# FLD_Logic.net
KiCad netlist of a schematic drawn in EAGLE
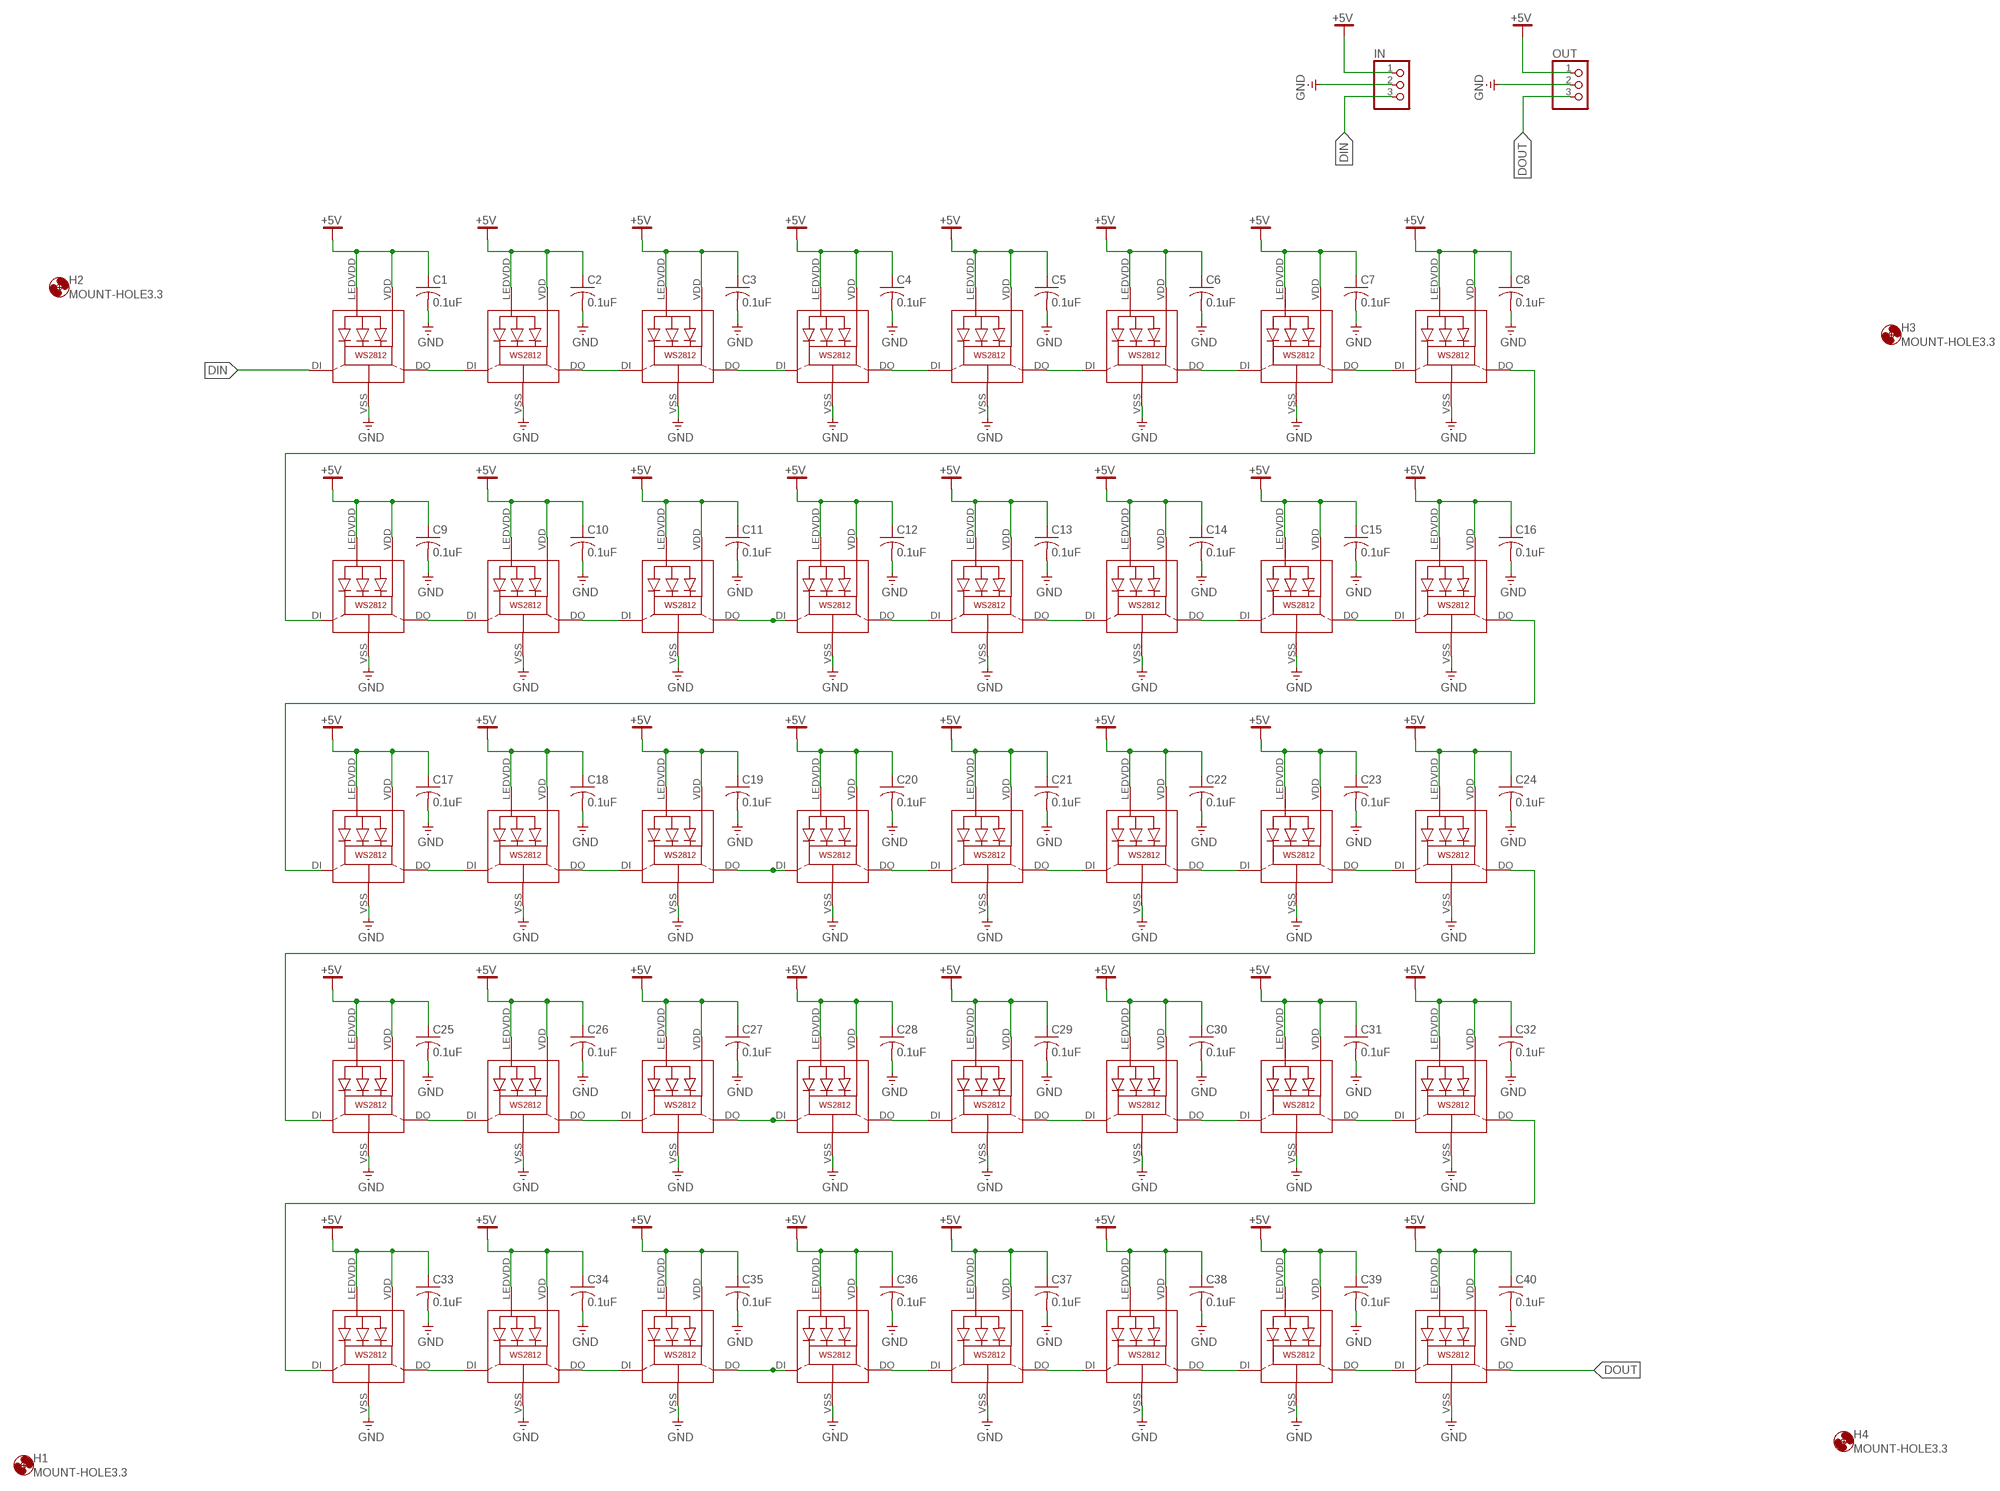
[diagram p0: schematic, sheet 1]

(export (version "E")
  (design (tool "Eeschema 10.0.6"))
  (components
    (comp (ref "C1")
      (value "0.1uF")
      (footprint "eagle-import:C0603")
      (libsource (lib "eagle-import") (part "C-USC0603"))
    )
    (comp (ref "C2")
      (value "0.1uF")
      (footprint "eagle-import:C0603")
      (libsource (lib "eagle-import") (part "C-USC0603"))
    )
    (comp (ref "C3")
      (value "0.1uF")
      (footprint "eagle-import:C0603")
      (libsource (lib "eagle-import") (part "C-USC0603"))
    )
    (comp (ref "C4")
      (value "0.1uF")
      (footprint "eagle-import:C0603")
      (libsource (lib "eagle-import") (part "C-USC0603"))
    )
    (comp (ref "C5")
      (value "0.1uF")
      (footprint "eagle-import:C0603")
      (libsource (lib "eagle-import") (part "C-USC0603"))
    )
    (comp (ref "C6")
      (value "0.1uF")
      (footprint "eagle-import:C0603")
      (libsource (lib "eagle-import") (part "C-USC0603"))
    )
    (comp (ref "C7")
      (value "0.1uF")
      (footprint "eagle-import:C0603")
      (libsource (lib "eagle-import") (part "C-USC0603"))
    )
    (comp (ref "C8")
      (value "0.1uF")
      (footprint "eagle-import:C0603")
      (libsource (lib "eagle-import") (part "C-USC0603"))
    )
    (comp (ref "C9")
      (value "0.1uF")
      (footprint "eagle-import:C0603")
      (libsource (lib "eagle-import") (part "C-USC0603"))
    )
    (comp (ref "C10")
      (value "0.1uF")
      (footprint "eagle-import:C0603")
      (libsource (lib "eagle-import") (part "C-USC0603"))
    )
    (comp (ref "C11")
      (value "0.1uF")
      (footprint "eagle-import:C0603")
      (libsource (lib "eagle-import") (part "C-USC0603"))
    )
    (comp (ref "C12")
      (value "0.1uF")
      (footprint "eagle-import:C0603")
      (libsource (lib "eagle-import") (part "C-USC0603"))
    )
    (comp (ref "C13")
      (value "0.1uF")
      (footprint "eagle-import:C0603")
      (libsource (lib "eagle-import") (part "C-USC0603"))
    )
    (comp (ref "C14")
      (value "0.1uF")
      (footprint "eagle-import:C0603")
      (libsource (lib "eagle-import") (part "C-USC0603"))
    )
    (comp (ref "C15")
      (value "0.1uF")
      (footprint "eagle-import:C0603")
      (libsource (lib "eagle-import") (part "C-USC0603"))
    )
    (comp (ref "C16")
      (value "0.1uF")
      (footprint "eagle-import:C0603")
      (libsource (lib "eagle-import") (part "C-USC0603"))
    )
    (comp (ref "C17")
      (value "0.1uF")
      (footprint "eagle-import:C0603")
      (libsource (lib "eagle-import") (part "C-USC0603"))
    )
    (comp (ref "C18")
      (value "0.1uF")
      (footprint "eagle-import:C0603")
      (libsource (lib "eagle-import") (part "C-USC0603"))
    )
    (comp (ref "C19")
      (value "0.1uF")
      (footprint "eagle-import:C0603")
      (libsource (lib "eagle-import") (part "C-USC0603"))
    )
    (comp (ref "C20")
      (value "0.1uF")
      (footprint "eagle-import:C0603")
      (libsource (lib "eagle-import") (part "C-USC0603"))
    )
    (comp (ref "C21")
      (value "0.1uF")
      (footprint "eagle-import:C0603")
      (libsource (lib "eagle-import") (part "C-USC0603"))
    )
    (comp (ref "C22")
      (value "0.1uF")
      (footprint "eagle-import:C0603")
      (libsource (lib "eagle-import") (part "C-USC0603"))
    )
    (comp (ref "C23")
      (value "0.1uF")
      (footprint "eagle-import:C0603")
      (libsource (lib "eagle-import") (part "C-USC0603"))
    )
    (comp (ref "C24")
      (value "0.1uF")
      (footprint "eagle-import:C0603")
      (libsource (lib "eagle-import") (part "C-USC0603"))
    )
    (comp (ref "C25")
      (value "0.1uF")
      (footprint "eagle-import:C0603")
      (libsource (lib "eagle-import") (part "C-USC0603"))
    )
    (comp (ref "C26")
      (value "0.1uF")
      (footprint "eagle-import:C0603")
      (libsource (lib "eagle-import") (part "C-USC0603"))
    )
    (comp (ref "C27")
      (value "0.1uF")
      (footprint "eagle-import:C0603")
      (libsource (lib "eagle-import") (part "C-USC0603"))
    )
    (comp (ref "C28")
      (value "0.1uF")
      (footprint "eagle-import:C0603")
      (libsource (lib "eagle-import") (part "C-USC0603"))
    )
    (comp (ref "C29")
      (value "0.1uF")
      (footprint "eagle-import:C0603")
      (libsource (lib "eagle-import") (part "C-USC0603"))
    )
    (comp (ref "C30")
      (value "0.1uF")
      (footprint "eagle-import:C0603")
      (libsource (lib "eagle-import") (part "C-USC0603"))
    )
    (comp (ref "C31")
      (value "0.1uF")
      (footprint "eagle-import:C0603")
      (libsource (lib "eagle-import") (part "C-USC0603"))
    )
    (comp (ref "C32")
      (value "0.1uF")
      (footprint "eagle-import:C0603")
      (libsource (lib "eagle-import") (part "C-USC0603"))
    )
    (comp (ref "C33")
      (value "0.1uF")
      (footprint "eagle-import:C0603")
      (libsource (lib "eagle-import") (part "C-USC0603"))
    )
    (comp (ref "C34")
      (value "0.1uF")
      (footprint "eagle-import:C0603")
      (libsource (lib "eagle-import") (part "C-USC0603"))
    )
    (comp (ref "C35")
      (value "0.1uF")
      (footprint "eagle-import:C0603")
      (libsource (lib "eagle-import") (part "C-USC0603"))
    )
    (comp (ref "C36")
      (value "0.1uF")
      (footprint "eagle-import:C0603")
      (libsource (lib "eagle-import") (part "C-USC0603"))
    )
    (comp (ref "C37")
      (value "0.1uF")
      (footprint "eagle-import:C0603")
      (libsource (lib "eagle-import") (part "C-USC0603"))
    )
    (comp (ref "C38")
      (value "0.1uF")
      (footprint "eagle-import:C0603")
      (libsource (lib "eagle-import") (part "C-USC0603"))
    )
    (comp (ref "C39")
      (value "0.1uF")
      (footprint "eagle-import:C0603")
      (libsource (lib "eagle-import") (part "C-USC0603"))
    )
    (comp (ref "C40")
      (value "0.1uF")
      (footprint "eagle-import:C0603")
      (libsource (lib "eagle-import") (part "C-USC0603"))
    )
    (comp (ref "H1")
      (value "MOUNT-HOLE3.3")
      (footprint "eagle-import:3,3")
      (libsource (lib "eagle-import") (part "MOUNT-HOLE3.3"))
    )
    (comp (ref "H2")
      (value "MOUNT-HOLE3.3")
      (footprint "eagle-import:3,3")
      (libsource (lib "eagle-import") (part "MOUNT-HOLE3.3"))
    )
    (comp (ref "H3")
      (value "MOUNT-HOLE3.3")
      (footprint "eagle-import:3,3")
      (libsource (lib "eagle-import") (part "MOUNT-HOLE3.3"))
    )
    (comp (ref "H4")
      (value "MOUNT-HOLE3.3")
      (footprint "eagle-import:3,3")
      (libsource (lib "eagle-import") (part "MOUNT-HOLE3.3"))
    )
    (comp (ref "IN")
      (value "PINHD-1X3")
      (footprint "eagle-import:1X03")
      (libsource (lib "eagle-import") (part "PINHD-1X3"))
    )
    (comp (ref "LED1")
      (value "WS2812")
      (footprint "eagle-import:WS2812")
      (libsource (lib "eagle-import") (part "WS2812"))
    )
    (comp (ref "LED2")
      (value "WS2812")
      (footprint "eagle-import:WS2812")
      (libsource (lib "eagle-import") (part "WS2812"))
    )
    (comp (ref "LED3")
      (value "WS2812")
      (footprint "eagle-import:WS2812")
      (libsource (lib "eagle-import") (part "WS2812"))
    )
    (comp (ref "LED4")
      (value "WS2812")
      (footprint "eagle-import:WS2812")
      (libsource (lib "eagle-import") (part "WS2812"))
    )
    (comp (ref "LED5")
      (value "WS2812")
      (footprint "eagle-import:WS2812")
      (libsource (lib "eagle-import") (part "WS2812"))
    )
    (comp (ref "LED6")
      (value "WS2812")
      (footprint "eagle-import:WS2812")
      (libsource (lib "eagle-import") (part "WS2812"))
    )
    (comp (ref "LED7")
      (value "WS2812")
      (footprint "eagle-import:WS2812")
      (libsource (lib "eagle-import") (part "WS2812"))
    )
    (comp (ref "LED8")
      (value "WS2812")
      (footprint "eagle-import:WS2812")
      (libsource (lib "eagle-import") (part "WS2812"))
    )
    (comp (ref "LED9")
      (value "WS2812")
      (footprint "eagle-import:WS2812")
      (libsource (lib "eagle-import") (part "WS2812"))
    )
    (comp (ref "LED10")
      (value "WS2812")
      (footprint "eagle-import:WS2812")
      (libsource (lib "eagle-import") (part "WS2812"))
    )
    (comp (ref "LED11")
      (value "WS2812")
      (footprint "eagle-import:WS2812")
      (libsource (lib "eagle-import") (part "WS2812"))
    )
    (comp (ref "LED12")
      (value "WS2812")
      (footprint "eagle-import:WS2812")
      (libsource (lib "eagle-import") (part "WS2812"))
    )
    (comp (ref "LED13")
      (value "WS2812")
      (footprint "eagle-import:WS2812")
      (libsource (lib "eagle-import") (part "WS2812"))
    )
    (comp (ref "LED14")
      (value "WS2812")
      (footprint "eagle-import:WS2812")
      (libsource (lib "eagle-import") (part "WS2812"))
    )
    (comp (ref "LED15")
      (value "WS2812")
      (footprint "eagle-import:WS2812")
      (libsource (lib "eagle-import") (part "WS2812"))
    )
    (comp (ref "LED16")
      (value "WS2812")
      (footprint "eagle-import:WS2812")
      (libsource (lib "eagle-import") (part "WS2812"))
    )
    (comp (ref "LED17")
      (value "WS2812")
      (footprint "eagle-import:WS2812")
      (libsource (lib "eagle-import") (part "WS2812"))
    )
    (comp (ref "LED18")
      (value "WS2812")
      (footprint "eagle-import:WS2812")
      (libsource (lib "eagle-import") (part "WS2812"))
    )
    (comp (ref "LED19")
      (value "WS2812")
      (footprint "eagle-import:WS2812")
      (libsource (lib "eagle-import") (part "WS2812"))
    )
    (comp (ref "LED20")
      (value "WS2812")
      (footprint "eagle-import:WS2812")
      (libsource (lib "eagle-import") (part "WS2812"))
    )
    (comp (ref "LED21")
      (value "WS2812")
      (footprint "eagle-import:WS2812")
      (libsource (lib "eagle-import") (part "WS2812"))
    )
    (comp (ref "LED22")
      (value "WS2812")
      (footprint "eagle-import:WS2812")
      (libsource (lib "eagle-import") (part "WS2812"))
    )
    (comp (ref "LED23")
      (value "WS2812")
      (footprint "eagle-import:WS2812")
      (libsource (lib "eagle-import") (part "WS2812"))
    )
    (comp (ref "LED24")
      (value "WS2812")
      (footprint "eagle-import:WS2812")
      (libsource (lib "eagle-import") (part "WS2812"))
    )
    (comp (ref "LED25")
      (value "WS2812")
      (footprint "eagle-import:WS2812")
      (libsource (lib "eagle-import") (part "WS2812"))
    )
    (comp (ref "LED26")
      (value "WS2812")
      (footprint "eagle-import:WS2812")
      (libsource (lib "eagle-import") (part "WS2812"))
    )
    (comp (ref "LED27")
      (value "WS2812")
      (footprint "eagle-import:WS2812")
      (libsource (lib "eagle-import") (part "WS2812"))
    )
    (comp (ref "LED28")
      (value "WS2812")
      (footprint "eagle-import:WS2812")
      (libsource (lib "eagle-import") (part "WS2812"))
    )
    (comp (ref "LED29")
      (value "WS2812")
      (footprint "eagle-import:WS2812")
      (libsource (lib "eagle-import") (part "WS2812"))
    )
    (comp (ref "LED30")
      (value "WS2812")
      (footprint "eagle-import:WS2812")
      (libsource (lib "eagle-import") (part "WS2812"))
    )
    (comp (ref "LED31")
      (value "WS2812")
      (footprint "eagle-import:WS2812")
      (libsource (lib "eagle-import") (part "WS2812"))
    )
    (comp (ref "LED32")
      (value "WS2812")
      (footprint "eagle-import:WS2812")
      (libsource (lib "eagle-import") (part "WS2812"))
    )
    (comp (ref "LED33")
      (value "WS2812")
      (footprint "eagle-import:WS2812")
      (libsource (lib "eagle-import") (part "WS2812"))
    )
    (comp (ref "LED34")
      (value "WS2812")
      (footprint "eagle-import:WS2812")
      (libsource (lib "eagle-import") (part "WS2812"))
    )
    (comp (ref "LED35")
      (value "WS2812")
      (footprint "eagle-import:WS2812")
      (libsource (lib "eagle-import") (part "WS2812"))
    )
    (comp (ref "LED36")
      (value "WS2812")
      (footprint "eagle-import:WS2812")
      (libsource (lib "eagle-import") (part "WS2812"))
    )
    (comp (ref "LED37")
      (value "WS2812")
      (footprint "eagle-import:WS2812")
      (libsource (lib "eagle-import") (part "WS2812"))
    )
    (comp (ref "LED38")
      (value "WS2812")
      (footprint "eagle-import:WS2812")
      (libsource (lib "eagle-import") (part "WS2812"))
    )
    (comp (ref "LED39")
      (value "WS2812")
      (footprint "eagle-import:WS2812")
      (libsource (lib "eagle-import") (part "WS2812"))
    )
    (comp (ref "LED40")
      (value "WS2812")
      (footprint "eagle-import:WS2812")
      (libsource (lib "eagle-import") (part "WS2812"))
    )
    (comp (ref "OUT")
      (value "PINHD-1X3")
      (footprint "eagle-import:1X03")
      (libsource (lib "eagle-import") (part "PINHD-1X3"))
    )
  )
  (nets
    (net (code "1") (name "+5V") (class "Default")
      (node (ref "C1") (pin "1") (pinfunction "1_1") (pintype "passive"))
      (node (ref "C10") (pin "1") (pinfunction "1_1") (pintype "passive"))
      (node (ref "C11") (pin "1") (pinfunction "1_1") (pintype "passive"))
      (node (ref "C12") (pin "1") (pinfunction "1_1") (pintype "passive"))
      (node (ref "C13") (pin "1") (pinfunction "1_1") (pintype "passive"))
      (node (ref "C14") (pin "1") (pinfunction "1_1") (pintype "passive"))
      (node (ref "C15") (pin "1") (pinfunction "1_1") (pintype "passive"))
      (node (ref "C16") (pin "1") (pinfunction "1_1") (pintype "passive"))
      (node (ref "C17") (pin "1") (pinfunction "1_1") (pintype "passive"))
      (node (ref "C18") (pin "1") (pinfunction "1_1") (pintype "passive"))
      (node (ref "C19") (pin "1") (pinfunction "1_1") (pintype "passive"))
      (node (ref "C2") (pin "1") (pinfunction "1_1") (pintype "passive"))
      (node (ref "C20") (pin "1") (pinfunction "1_1") (pintype "passive"))
      (node (ref "C21") (pin "1") (pinfunction "1_1") (pintype "passive"))
      (node (ref "C22") (pin "1") (pinfunction "1_1") (pintype "passive"))
      (node (ref "C23") (pin "1") (pinfunction "1_1") (pintype "passive"))
      (node (ref "C24") (pin "1") (pinfunction "1_1") (pintype "passive"))
      (node (ref "C25") (pin "1") (pinfunction "1_1") (pintype "passive"))
      (node (ref "C26") (pin "1") (pinfunction "1_1") (pintype "passive"))
      (node (ref "C27") (pin "1") (pinfunction "1_1") (pintype "passive"))
      (node (ref "C28") (pin "1") (pinfunction "1_1") (pintype "passive"))
      (node (ref "C29") (pin "1") (pinfunction "1_1") (pintype "passive"))
      (node (ref "C3") (pin "1") (pinfunction "1_1") (pintype "passive"))
      (node (ref "C30") (pin "1") (pinfunction "1_1") (pintype "passive"))
      (node (ref "C31") (pin "1") (pinfunction "1_1") (pintype "passive"))
      (node (ref "C32") (pin "1") (pinfunction "1_1") (pintype "passive"))
      (node (ref "C33") (pin "1") (pinfunction "1_1") (pintype "passive"))
      (node (ref "C34") (pin "1") (pinfunction "1_1") (pintype "passive"))
      (node (ref "C35") (pin "1") (pinfunction "1_1") (pintype "passive"))
      (node (ref "C36") (pin "1") (pinfunction "1_1") (pintype "passive"))
      (node (ref "C37") (pin "1") (pinfunction "1_1") (pintype "passive"))
      (node (ref "C38") (pin "1") (pinfunction "1_1") (pintype "passive"))
      (node (ref "C39") (pin "1") (pinfunction "1_1") (pintype "passive"))
      (node (ref "C4") (pin "1") (pinfunction "1_1") (pintype "passive"))
      (node (ref "C40") (pin "1") (pinfunction "1_1") (pintype "passive"))
      (node (ref "C5") (pin "1") (pinfunction "1_1") (pintype "passive"))
      (node (ref "C6") (pin "1") (pinfunction "1_1") (pintype "passive"))
      (node (ref "C7") (pin "1") (pinfunction "1_1") (pintype "passive"))
      (node (ref "C8") (pin "1") (pinfunction "1_1") (pintype "passive"))
      (node (ref "C9") (pin "1") (pinfunction "1_1") (pintype "passive"))
      (node (ref "IN") (pin "1") (pinfunction "1_1") (pintype "passive"))
      (node (ref "LED1") (pin "LEDVDD") (pinfunction "LEDVDD_LEDVDD") (pintype "power_in"))
      (node (ref "LED1") (pin "VDD") (pinfunction "VDD_VDD") (pintype "power_in"))
      (node (ref "LED10") (pin "LEDVDD") (pinfunction "LEDVDD_LEDVDD") (pintype "power_in"))
      (node (ref "LED10") (pin "VDD") (pinfunction "VDD_VDD") (pintype "power_in"))
      (node (ref "LED11") (pin "LEDVDD") (pinfunction "LEDVDD_LEDVDD") (pintype "power_in"))
      (node (ref "LED11") (pin "VDD") (pinfunction "VDD_VDD") (pintype "power_in"))
      (node (ref "LED12") (pin "LEDVDD") (pinfunction "LEDVDD_LEDVDD") (pintype "power_in"))
      (node (ref "LED12") (pin "VDD") (pinfunction "VDD_VDD") (pintype "power_in"))
      (node (ref "LED13") (pin "LEDVDD") (pinfunction "LEDVDD_LEDVDD") (pintype "power_in"))
      (node (ref "LED13") (pin "VDD") (pinfunction "VDD_VDD") (pintype "power_in"))
      (node (ref "LED14") (pin "LEDVDD") (pinfunction "LEDVDD_LEDVDD") (pintype "power_in"))
      (node (ref "LED14") (pin "VDD") (pinfunction "VDD_VDD") (pintype "power_in"))
      (node (ref "LED15") (pin "LEDVDD") (pinfunction "LEDVDD_LEDVDD") (pintype "power_in"))
      (node (ref "LED15") (pin "VDD") (pinfunction "VDD_VDD") (pintype "power_in"))
      (node (ref "LED16") (pin "LEDVDD") (pinfunction "LEDVDD_LEDVDD") (pintype "power_in"))
      (node (ref "LED16") (pin "VDD") (pinfunction "VDD_VDD") (pintype "power_in"))
      (node (ref "LED17") (pin "LEDVDD") (pinfunction "LEDVDD_LEDVDD") (pintype "power_in"))
      (node (ref "LED17") (pin "VDD") (pinfunction "VDD_VDD") (pintype "power_in"))
      (node (ref "LED18") (pin "LEDVDD") (pinfunction "LEDVDD_LEDVDD") (pintype "power_in"))
      (node (ref "LED18") (pin "VDD") (pinfunction "VDD_VDD") (pintype "power_in"))
      (node (ref "LED19") (pin "LEDVDD") (pinfunction "LEDVDD_LEDVDD") (pintype "power_in"))
      (node (ref "LED19") (pin "VDD") (pinfunction "VDD_VDD") (pintype "power_in"))
      (node (ref "LED2") (pin "LEDVDD") (pinfunction "LEDVDD_LEDVDD") (pintype "power_in"))
      (node (ref "LED2") (pin "VDD") (pinfunction "VDD_VDD") (pintype "power_in"))
      (node (ref "LED20") (pin "LEDVDD") (pinfunction "LEDVDD_LEDVDD") (pintype "power_in"))
      (node (ref "LED20") (pin "VDD") (pinfunction "VDD_VDD") (pintype "power_in"))
      (node (ref "LED21") (pin "LEDVDD") (pinfunction "LEDVDD_LEDVDD") (pintype "power_in"))
      (node (ref "LED21") (pin "VDD") (pinfunction "VDD_VDD") (pintype "power_in"))
      (node (ref "LED22") (pin "LEDVDD") (pinfunction "LEDVDD_LEDVDD") (pintype "power_in"))
      (node (ref "LED22") (pin "VDD") (pinfunction "VDD_VDD") (pintype "power_in"))
      (node (ref "LED23") (pin "LEDVDD") (pinfunction "LEDVDD_LEDVDD") (pintype "power_in"))
      (node (ref "LED23") (pin "VDD") (pinfunction "VDD_VDD") (pintype "power_in"))
      (node (ref "LED24") (pin "LEDVDD") (pinfunction "LEDVDD_LEDVDD") (pintype "power_in"))
      (node (ref "LED24") (pin "VDD") (pinfunction "VDD_VDD") (pintype "power_in"))
      (node (ref "LED25") (pin "LEDVDD") (pinfunction "LEDVDD_LEDVDD") (pintype "power_in"))
      (node (ref "LED25") (pin "VDD") (pinfunction "VDD_VDD") (pintype "power_in"))
      (node (ref "LED26") (pin "LEDVDD") (pinfunction "LEDVDD_LEDVDD") (pintype "power_in"))
      (node (ref "LED26") (pin "VDD") (pinfunction "VDD_VDD") (pintype "power_in"))
      (node (ref "LED27") (pin "LEDVDD") (pinfunction "LEDVDD_LEDVDD") (pintype "power_in"))
      (node (ref "LED27") (pin "VDD") (pinfunction "VDD_VDD") (pintype "power_in"))
      (node (ref "LED28") (pin "LEDVDD") (pinfunction "LEDVDD_LEDVDD") (pintype "power_in"))
      (node (ref "LED28") (pin "VDD") (pinfunction "VDD_VDD") (pintype "power_in"))
      (node (ref "LED29") (pin "LEDVDD") (pinfunction "LEDVDD_LEDVDD") (pintype "power_in"))
      (node (ref "LED29") (pin "VDD") (pinfunction "VDD_VDD") (pintype "power_in"))
      (node (ref "LED3") (pin "LEDVDD") (pinfunction "LEDVDD_LEDVDD") (pintype "power_in"))
      (node (ref "LED3") (pin "VDD") (pinfunction "VDD_VDD") (pintype "power_in"))
      (node (ref "LED30") (pin "LEDVDD") (pinfunction "LEDVDD_LEDVDD") (pintype "power_in"))
      (node (ref "LED30") (pin "VDD") (pinfunction "VDD_VDD") (pintype "power_in"))
      (node (ref "LED31") (pin "LEDVDD") (pinfunction "LEDVDD_LEDVDD") (pintype "power_in"))
      (node (ref "LED31") (pin "VDD") (pinfunction "VDD_VDD") (pintype "power_in"))
      (node (ref "LED32") (pin "LEDVDD") (pinfunction "LEDVDD_LEDVDD") (pintype "power_in"))
      (node (ref "LED32") (pin "VDD") (pinfunction "VDD_VDD") (pintype "power_in"))
      (node (ref "LED33") (pin "LEDVDD") (pinfunction "LEDVDD_LEDVDD") (pintype "power_in"))
      (node (ref "LED33") (pin "VDD") (pinfunction "VDD_VDD") (pintype "power_in"))
      (node (ref "LED34") (pin "LEDVDD") (pinfunction "LEDVDD_LEDVDD") (pintype "power_in"))
      (node (ref "LED34") (pin "VDD") (pinfunction "VDD_VDD") (pintype "power_in"))
      (node (ref "LED35") (pin "LEDVDD") (pinfunction "LEDVDD_LEDVDD") (pintype "power_in"))
      (node (ref "LED35") (pin "VDD") (pinfunction "VDD_VDD") (pintype "power_in"))
      (node (ref "LED36") (pin "LEDVDD") (pinfunction "LEDVDD_LEDVDD") (pintype "power_in"))
      (node (ref "LED36") (pin "VDD") (pinfunction "VDD_VDD") (pintype "power_in"))
      (node (ref "LED37") (pin "LEDVDD") (pinfunction "LEDVDD_LEDVDD") (pintype "power_in"))
      (node (ref "LED37") (pin "VDD") (pinfunction "VDD_VDD") (pintype "power_in"))
      (node (ref "LED38") (pin "LEDVDD") (pinfunction "LEDVDD_LEDVDD") (pintype "power_in"))
      (node (ref "LED38") (pin "VDD") (pinfunction "VDD_VDD") (pintype "power_in"))
      (node (ref "LED39") (pin "LEDVDD") (pinfunction "LEDVDD_LEDVDD") (pintype "power_in"))
      (node (ref "LED39") (pin "VDD") (pinfunction "VDD_VDD") (pintype "power_in"))
      (node (ref "LED4") (pin "LEDVDD") (pinfunction "LEDVDD_LEDVDD") (pintype "power_in"))
      (node (ref "LED4") (pin "VDD") (pinfunction "VDD_VDD") (pintype "power_in"))
      (node (ref "LED40") (pin "LEDVDD") (pinfunction "LEDVDD_LEDVDD") (pintype "power_in"))
      (node (ref "LED40") (pin "VDD") (pinfunction "VDD_VDD") (pintype "power_in"))
      (node (ref "LED5") (pin "LEDVDD") (pinfunction "LEDVDD_LEDVDD") (pintype "power_in"))
      (node (ref "LED5") (pin "VDD") (pinfunction "VDD_VDD") (pintype "power_in"))
      (node (ref "LED6") (pin "LEDVDD") (pinfunction "LEDVDD_LEDVDD") (pintype "power_in"))
      (node (ref "LED6") (pin "VDD") (pinfunction "VDD_VDD") (pintype "power_in"))
      (node (ref "LED7") (pin "LEDVDD") (pinfunction "LEDVDD_LEDVDD") (pintype "power_in"))
      (node (ref "LED7") (pin "VDD") (pinfunction "VDD_VDD") (pintype "power_in"))
      (node (ref "LED8") (pin "LEDVDD") (pinfunction "LEDVDD_LEDVDD") (pintype "power_in"))
      (node (ref "LED8") (pin "VDD") (pinfunction "VDD_VDD") (pintype "power_in"))
      (node (ref "LED9") (pin "LEDVDD") (pinfunction "LEDVDD_LEDVDD") (pintype "power_in"))
      (node (ref "LED9") (pin "VDD") (pinfunction "VDD_VDD") (pintype "power_in"))
      (node (ref "OUT") (pin "1") (pinfunction "1_1") (pintype "passive"))
    )
    (net (code "2") (name "DIN") (class "Default")
      (node (ref "IN") (pin "3") (pinfunction "3_3") (pintype "passive"))
      (node (ref "LED1") (pin "DI") (pinfunction "DI_DI") (pintype "input"))
    )
    (net (code "3") (name "DOUT") (class "Default")
      (node (ref "LED40") (pin "DO") (pinfunction "DO_DO") (pintype "output"))
      (node (ref "OUT") (pin "3") (pinfunction "3_3") (pintype "passive"))
    )
    (net (code "4") (name "GND") (class "Default")
      (node (ref "C1") (pin "2") (pinfunction "2_2") (pintype "passive"))
      (node (ref "C10") (pin "2") (pinfunction "2_2") (pintype "passive"))
      (node (ref "C11") (pin "2") (pinfunction "2_2") (pintype "passive"))
      (node (ref "C12") (pin "2") (pinfunction "2_2") (pintype "passive"))
      (node (ref "C13") (pin "2") (pinfunction "2_2") (pintype "passive"))
      (node (ref "C14") (pin "2") (pinfunction "2_2") (pintype "passive"))
      (node (ref "C15") (pin "2") (pinfunction "2_2") (pintype "passive"))
      (node (ref "C16") (pin "2") (pinfunction "2_2") (pintype "passive"))
      (node (ref "C17") (pin "2") (pinfunction "2_2") (pintype "passive"))
      (node (ref "C18") (pin "2") (pinfunction "2_2") (pintype "passive"))
      (node (ref "C19") (pin "2") (pinfunction "2_2") (pintype "passive"))
      (node (ref "C2") (pin "2") (pinfunction "2_2") (pintype "passive"))
      (node (ref "C20") (pin "2") (pinfunction "2_2") (pintype "passive"))
      (node (ref "C21") (pin "2") (pinfunction "2_2") (pintype "passive"))
      (node (ref "C22") (pin "2") (pinfunction "2_2") (pintype "passive"))
      (node (ref "C23") (pin "2") (pinfunction "2_2") (pintype "passive"))
      (node (ref "C24") (pin "2") (pinfunction "2_2") (pintype "passive"))
      (node (ref "C25") (pin "2") (pinfunction "2_2") (pintype "passive"))
      (node (ref "C26") (pin "2") (pinfunction "2_2") (pintype "passive"))
      (node (ref "C27") (pin "2") (pinfunction "2_2") (pintype "passive"))
      (node (ref "C28") (pin "2") (pinfunction "2_2") (pintype "passive"))
      (node (ref "C29") (pin "2") (pinfunction "2_2") (pintype "passive"))
      (node (ref "C3") (pin "2") (pinfunction "2_2") (pintype "passive"))
      (node (ref "C30") (pin "2") (pinfunction "2_2") (pintype "passive"))
      (node (ref "C31") (pin "2") (pinfunction "2_2") (pintype "passive"))
      (node (ref "C32") (pin "2") (pinfunction "2_2") (pintype "passive"))
      (node (ref "C33") (pin "2") (pinfunction "2_2") (pintype "passive"))
      (node (ref "C34") (pin "2") (pinfunction "2_2") (pintype "passive"))
      (node (ref "C35") (pin "2") (pinfunction "2_2") (pintype "passive"))
      (node (ref "C36") (pin "2") (pinfunction "2_2") (pintype "passive"))
      (node (ref "C37") (pin "2") (pinfunction "2_2") (pintype "passive"))
      (node (ref "C38") (pin "2") (pinfunction "2_2") (pintype "passive"))
      (node (ref "C39") (pin "2") (pinfunction "2_2") (pintype "passive"))
      (node (ref "C4") (pin "2") (pinfunction "2_2") (pintype "passive"))
      (node (ref "C40") (pin "2") (pinfunction "2_2") (pintype "passive"))
      (node (ref "C5") (pin "2") (pinfunction "2_2") (pintype "passive"))
      (node (ref "C6") (pin "2") (pinfunction "2_2") (pintype "passive"))
      (node (ref "C7") (pin "2") (pinfunction "2_2") (pintype "passive"))
      (node (ref "C8") (pin "2") (pinfunction "2_2") (pintype "passive"))
      (node (ref "C9") (pin "2") (pinfunction "2_2") (pintype "passive"))
      (node (ref "IN") (pin "2") (pinfunction "2_2") (pintype "passive"))
      (node (ref "LED1") (pin "VSS") (pinfunction "GND_VSS") (pintype "power_in"))
      (node (ref "LED10") (pin "VSS") (pinfunction "GND_VSS") (pintype "power_in"))
      (node (ref "LED11") (pin "VSS") (pinfunction "GND_VSS") (pintype "power_in"))
      (node (ref "LED12") (pin "VSS") (pinfunction "GND_VSS") (pintype "power_in"))
      (node (ref "LED13") (pin "VSS") (pinfunction "GND_VSS") (pintype "power_in"))
      (node (ref "LED14") (pin "VSS") (pinfunction "GND_VSS") (pintype "power_in"))
      (node (ref "LED15") (pin "VSS") (pinfunction "GND_VSS") (pintype "power_in"))
      (node (ref "LED16") (pin "VSS") (pinfunction "GND_VSS") (pintype "power_in"))
      (node (ref "LED17") (pin "VSS") (pinfunction "GND_VSS") (pintype "power_in"))
      (node (ref "LED18") (pin "VSS") (pinfunction "GND_VSS") (pintype "power_in"))
      (node (ref "LED19") (pin "VSS") (pinfunction "GND_VSS") (pintype "power_in"))
      (node (ref "LED2") (pin "VSS") (pinfunction "GND_VSS") (pintype "power_in"))
      (node (ref "LED20") (pin "VSS") (pinfunction "GND_VSS") (pintype "power_in"))
      (node (ref "LED21") (pin "VSS") (pinfunction "GND_VSS") (pintype "power_in"))
      (node (ref "LED22") (pin "VSS") (pinfunction "GND_VSS") (pintype "power_in"))
      (node (ref "LED23") (pin "VSS") (pinfunction "GND_VSS") (pintype "power_in"))
      (node (ref "LED24") (pin "VSS") (pinfunction "GND_VSS") (pintype "power_in"))
      (node (ref "LED25") (pin "VSS") (pinfunction "GND_VSS") (pintype "power_in"))
      (node (ref "LED26") (pin "VSS") (pinfunction "GND_VSS") (pintype "power_in"))
      (node (ref "LED27") (pin "VSS") (pinfunction "GND_VSS") (pintype "power_in"))
      (node (ref "LED28") (pin "VSS") (pinfunction "GND_VSS") (pintype "power_in"))
      (node (ref "LED29") (pin "VSS") (pinfunction "GND_VSS") (pintype "power_in"))
      (node (ref "LED3") (pin "VSS") (pinfunction "GND_VSS") (pintype "power_in"))
      (node (ref "LED30") (pin "VSS") (pinfunction "GND_VSS") (pintype "power_in"))
      (node (ref "LED31") (pin "VSS") (pinfunction "GND_VSS") (pintype "power_in"))
      (node (ref "LED32") (pin "VSS") (pinfunction "GND_VSS") (pintype "power_in"))
      (node (ref "LED33") (pin "VSS") (pinfunction "GND_VSS") (pintype "power_in"))
      (node (ref "LED34") (pin "VSS") (pinfunction "GND_VSS") (pintype "power_in"))
      (node (ref "LED35") (pin "VSS") (pinfunction "GND_VSS") (pintype "power_in"))
      (node (ref "LED36") (pin "VSS") (pinfunction "GND_VSS") (pintype "power_in"))
      (node (ref "LED37") (pin "VSS") (pinfunction "GND_VSS") (pintype "power_in"))
      (node (ref "LED38") (pin "VSS") (pinfunction "GND_VSS") (pintype "power_in"))
      (node (ref "LED39") (pin "VSS") (pinfunction "GND_VSS") (pintype "power_in"))
      (node (ref "LED4") (pin "VSS") (pinfunction "GND_VSS") (pintype "power_in"))
      (node (ref "LED40") (pin "VSS") (pinfunction "GND_VSS") (pintype "power_in"))
      (node (ref "LED5") (pin "VSS") (pinfunction "GND_VSS") (pintype "power_in"))
      (node (ref "LED6") (pin "VSS") (pinfunction "GND_VSS") (pintype "power_in"))
      (node (ref "LED7") (pin "VSS") (pinfunction "GND_VSS") (pintype "power_in"))
      (node (ref "LED8") (pin "VSS") (pinfunction "GND_VSS") (pintype "power_in"))
      (node (ref "LED9") (pin "VSS") (pinfunction "GND_VSS") (pintype "power_in"))
      (node (ref "OUT") (pin "2") (pinfunction "2_2") (pintype "passive"))
    )
    (net (code "5") (name "Net-(LED1-PadDO)") (class "Default")
      (node (ref "LED1") (pin "DO") (pinfunction "DO_DO") (pintype "output"))
      (node (ref "LED2") (pin "DI") (pinfunction "DI_DI") (pintype "input"))
    )
    (net (code "6") (name "Net-(LED2-PadDO)") (class "Default")
      (node (ref "LED2") (pin "DO") (pinfunction "DO_DO") (pintype "output"))
      (node (ref "LED3") (pin "DI") (pinfunction "DI_DI") (pintype "input"))
    )
    (net (code "7") (name "Net-(LED4-PadDO)") (class "Default")
      (node (ref "LED4") (pin "DO") (pinfunction "DO_DO") (pintype "output"))
      (node (ref "LED5") (pin "DI") (pinfunction "DI_DI") (pintype "input"))
    )
    (net (code "8") (name "Net-(LED5-PadDO)") (class "Default")
      (node (ref "LED5") (pin "DO") (pinfunction "DO_DO") (pintype "output"))
      (node (ref "LED6") (pin "DI") (pinfunction "DI_DI") (pintype "input"))
    )
    (net (code "9") (name "Net-(LED6-PadDO)") (class "Default")
      (node (ref "LED6") (pin "DO") (pinfunction "DO_DO") (pintype "output"))
      (node (ref "LED7") (pin "DI") (pinfunction "DI_DI") (pintype "input"))
    )
    (net (code "10") (name "Net-(LED7-PadDO)") (class "Default")
      (node (ref "LED7") (pin "DO") (pinfunction "DO_DO") (pintype "output"))
      (node (ref "LED8") (pin "DI") (pinfunction "DI_DI") (pintype "input"))
    )
    (net (code "11") (name "Net-(LED10-PadDI)") (class "Default")
      (node (ref "LED10") (pin "DI") (pinfunction "DI_DI") (pintype "input"))
      (node (ref "LED9") (pin "DO") (pinfunction "DO_DO") (pintype "output"))
    )
    (net (code "12") (name "Net-(LED10-PadDO)") (class "Default")
      (node (ref "LED10") (pin "DO") (pinfunction "DO_DO") (pintype "output"))
      (node (ref "LED11") (pin "DI") (pinfunction "DI_DI") (pintype "input"))
    )
    (net (code "13") (name "Net-(LED11-PadDO)") (class "Default")
      (node (ref "LED11") (pin "DO") (pinfunction "DO_DO") (pintype "output"))
      (node (ref "LED12") (pin "DI") (pinfunction "DI_DI") (pintype "input"))
    )
    (net (code "14") (name "Net-(LED12-PadDO)") (class "Default")
      (node (ref "LED12") (pin "DO") (pinfunction "DO_DO") (pintype "output"))
      (node (ref "LED13") (pin "DI") (pinfunction "DI_DI") (pintype "input"))
    )
    (net (code "15") (name "Net-(LED13-PadDO)") (class "Default")
      (node (ref "LED13") (pin "DO") (pinfunction "DO_DO") (pintype "output"))
      (node (ref "LED14") (pin "DI") (pinfunction "DI_DI") (pintype "input"))
    )
    (net (code "16") (name "Net-(LED14-PadDO)") (class "Default")
      (node (ref "LED14") (pin "DO") (pinfunction "DO_DO") (pintype "output"))
      (node (ref "LED15") (pin "DI") (pinfunction "DI_DI") (pintype "input"))
    )
    (net (code "17") (name "Net-(LED15-PadDO)") (class "Default")
      (node (ref "LED15") (pin "DO") (pinfunction "DO_DO") (pintype "output"))
      (node (ref "LED16") (pin "DI") (pinfunction "DI_DI") (pintype "input"))
    )
    (net (code "18") (name "Net-(LED17-PadDO)") (class "Default")
      (node (ref "LED17") (pin "DO") (pinfunction "DO_DO") (pintype "output"))
      (node (ref "LED18") (pin "DI") (pinfunction "DI_DI") (pintype "input"))
    )
    (net (code "19") (name "Net-(LED18-PadDO)") (class "Default")
      (node (ref "LED18") (pin "DO") (pinfunction "DO_DO") (pintype "output"))
      (node (ref "LED19") (pin "DI") (pinfunction "DI_DI") (pintype "input"))
    )
    (net (code "20") (name "Net-(LED19-PadDO)") (class "Default")
      (node (ref "LED19") (pin "DO") (pinfunction "DO_DO") (pintype "output"))
      (node (ref "LED20") (pin "DI") (pinfunction "DI_DI") (pintype "input"))
    )
    (net (code "21") (name "Net-(LED20-PadDO)") (class "Default")
      (node (ref "LED20") (pin "DO") (pinfunction "DO_DO") (pintype "output"))
      (node (ref "LED21") (pin "DI") (pinfunction "DI_DI") (pintype "input"))
    )
    (net (code "22") (name "Net-(LED21-PadDO)") (class "Default")
      (node (ref "LED21") (pin "DO") (pinfunction "DO_DO") (pintype "output"))
      (node (ref "LED22") (pin "DI") (pinfunction "DI_DI") (pintype "input"))
    )
    (net (code "23") (name "Net-(LED22-PadDO)") (class "Default")
      (node (ref "LED22") (pin "DO") (pinfunction "DO_DO") (pintype "output"))
      (node (ref "LED23") (pin "DI") (pinfunction "DI_DI") (pintype "input"))
    )
    (net (code "24") (name "Net-(LED23-PadDO)") (class "Default")
      (node (ref "LED23") (pin "DO") (pinfunction "DO_DO") (pintype "output"))
      (node (ref "LED24") (pin "DI") (pinfunction "DI_DI") (pintype "input"))
    )
    (net (code "25") (name "Net-(LED25-PadDO)") (class "Default")
      (node (ref "LED25") (pin "DO") (pinfunction "DO_DO") (pintype "output"))
      (node (ref "LED26") (pin "DI") (pinfunction "DI_DI") (pintype "input"))
    )
    (net (code "26") (name "Net-(LED26-PadDO)") (class "Default")
      (node (ref "LED26") (pin "DO") (pinfunction "DO_DO") (pintype "output"))
      (node (ref "LED27") (pin "DI") (pinfunction "DI_DI") (pintype "input"))
    )
    (net (code "27") (name "Net-(LED27-PadDO)") (class "Default")
      (node (ref "LED27") (pin "DO") (pinfunction "DO_DO") (pintype "output"))
      (node (ref "LED28") (pin "DI") (pinfunction "DI_DI") (pintype "input"))
    )
    (net (code "28") (name "Net-(LED28-PadDO)") (class "Default")
      (node (ref "LED28") (pin "DO") (pinfunction "DO_DO") (pintype "output"))
      (node (ref "LED29") (pin "DI") (pinfunction "DI_DI") (pintype "input"))
    )
    (net (code "29") (name "Net-(LED29-PadDO)") (class "Default")
      (node (ref "LED29") (pin "DO") (pinfunction "DO_DO") (pintype "output"))
      (node (ref "LED30") (pin "DI") (pinfunction "DI_DI") (pintype "input"))
    )
    (net (code "30") (name "Net-(LED30-PadDO)") (class "Default")
      (node (ref "LED30") (pin "DO") (pinfunction "DO_DO") (pintype "output"))
      (node (ref "LED31") (pin "DI") (pinfunction "DI_DI") (pintype "input"))
    )
    (net (code "31") (name "Net-(LED31-PadDO)") (class "Default")
      (node (ref "LED31") (pin "DO") (pinfunction "DO_DO") (pintype "output"))
      (node (ref "LED32") (pin "DI") (pinfunction "DI_DI") (pintype "input"))
    )
    (net (code "32") (name "Net-(LED33-PadDO)") (class "Default")
      (node (ref "LED33") (pin "DO") (pinfunction "DO_DO") (pintype "output"))
      (node (ref "LED34") (pin "DI") (pinfunction "DI_DI") (pintype "input"))
    )
    (net (code "33") (name "Net-(LED34-PadDO)") (class "Default")
      (node (ref "LED34") (pin "DO") (pinfunction "DO_DO") (pintype "output"))
      (node (ref "LED35") (pin "DI") (pinfunction "DI_DI") (pintype "input"))
    )
    (net (code "34") (name "Net-(LED35-PadDO)") (class "Default")
      (node (ref "LED35") (pin "DO") (pinfunction "DO_DO") (pintype "output"))
      (node (ref "LED36") (pin "DI") (pinfunction "DI_DI") (pintype "input"))
    )
    (net (code "35") (name "Net-(LED36-PadDO)") (class "Default")
      (node (ref "LED36") (pin "DO") (pinfunction "DO_DO") (pintype "output"))
      (node (ref "LED37") (pin "DI") (pinfunction "DI_DI") (pintype "input"))
    )
    (net (code "36") (name "Net-(LED37-PadDO)") (class "Default")
      (node (ref "LED37") (pin "DO") (pinfunction "DO_DO") (pintype "output"))
      (node (ref "LED38") (pin "DI") (pinfunction "DI_DI") (pintype "input"))
    )
    (net (code "37") (name "Net-(LED38-PadDO)") (class "Default")
      (node (ref "LED38") (pin "DO") (pinfunction "DO_DO") (pintype "output"))
      (node (ref "LED39") (pin "DI") (pinfunction "DI_DI") (pintype "input"))
    )
    (net (code "38") (name "Net-(LED39-PadDO)") (class "Default")
      (node (ref "LED39") (pin "DO") (pinfunction "DO_DO") (pintype "output"))
      (node (ref "LED40") (pin "DI") (pinfunction "DI_DI") (pintype "input"))
    )
    (net (code "39") (name "unconnected-(LED3-PadDO)") (class "Default")
      (node (ref "LED3") (pin "DO") (pinfunction "DO_DO") (pintype "output"))
    )
    (net (code "40") (name "unconnected-(LED4-PadDI)") (class "Default")
      (node (ref "LED4") (pin "DI") (pinfunction "DI_DI") (pintype "input"))
    )
    (net (code "41") (name "unconnected-(LED8-PadDO)") (class "Default")
      (node (ref "LED8") (pin "DO") (pinfunction "DO_DO") (pintype "output"))
    )
    (net (code "42") (name "unconnected-(LED9-PadDI)") (class "Default")
      (node (ref "LED9") (pin "DI") (pinfunction "DI_DI") (pintype "input"))
    )
    (net (code "43") (name "unconnected-(LED16-PadDO)") (class "Default")
      (node (ref "LED16") (pin "DO") (pinfunction "DO_DO") (pintype "output"))
    )
    (net (code "44") (name "unconnected-(LED17-PadDI)") (class "Default")
      (node (ref "LED17") (pin "DI") (pinfunction "DI_DI") (pintype "input"))
    )
    (net (code "45") (name "unconnected-(LED24-PadDO)") (class "Default")
      (node (ref "LED24") (pin "DO") (pinfunction "DO_DO") (pintype "output"))
    )
    (net (code "46") (name "unconnected-(LED25-PadDI)") (class "Default")
      (node (ref "LED25") (pin "DI") (pinfunction "DI_DI") (pintype "input"))
    )
    (net (code "47") (name "unconnected-(LED32-PadDO)") (class "Default")
      (node (ref "LED32") (pin "DO") (pinfunction "DO_DO") (pintype "output"))
    )
    (net (code "48") (name "unconnected-(LED33-PadDI)") (class "Default")
      (node (ref "LED33") (pin "DI") (pinfunction "DI_DI") (pintype "input"))
    )
  )
)
